# ProPrj_Iris_One_2026-02-20.net
KiCad netlist of a schematic drawn in EasyEDA Pro
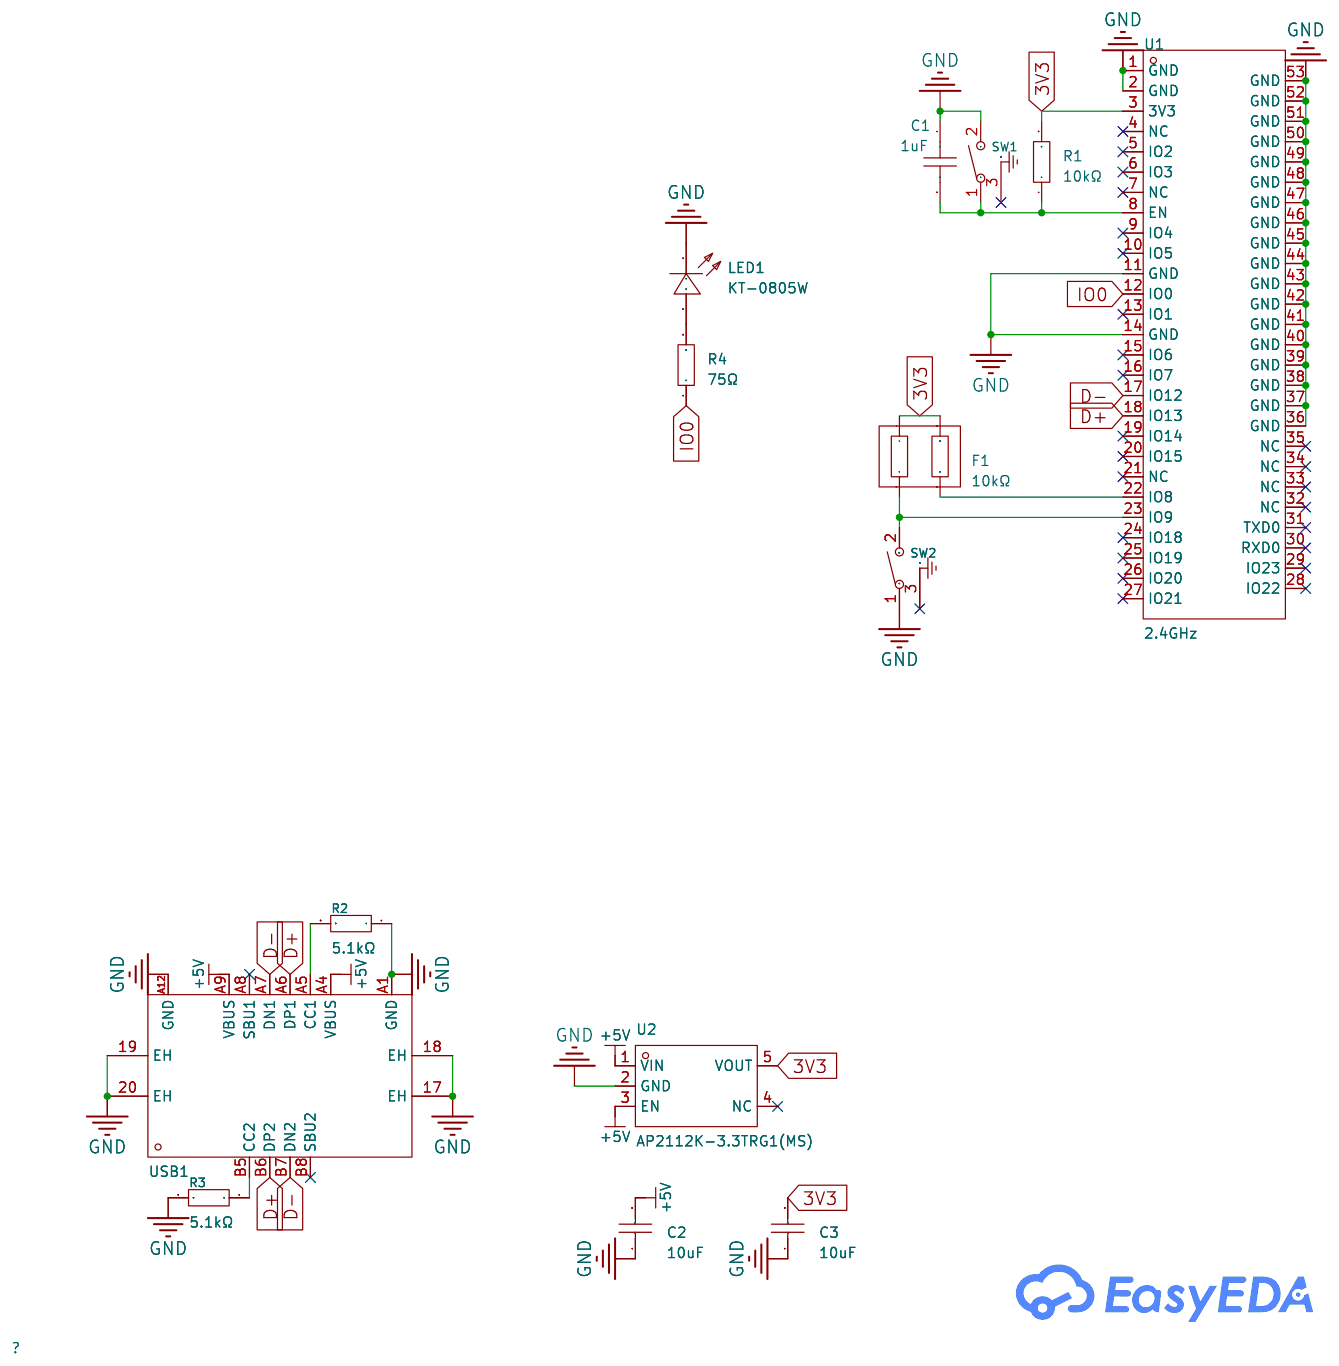
[diagram p0: schematic sheet]

(export (version "E")
  (design (tool "Eeschema 10.0.6"))
  (components
    (comp (ref "C1")
      (value "1uF")
      (footprint "easyedapro:C0402")
      (description "Capacitance:1uF Tolerance:±10% Tolerance:±10% Voltage Rating:25V Temperature Coefficient:X5R")
      (fields
        (field (name "Manufacturer Part") "CL05A105KA5NQNC")
        (field (name "Manufacturer") "SAMSUNG(三星)")
      )
      (libsource (lib "easyedapro") (part "CL05A105KA5NQNC"))
    )
    (comp (ref "C2")
      (value "10uF")
      (footprint "easyedapro:C0402")
      (description "Capacitance:10uF Tolerance:±20% Tolerance:±20% Voltage Rating:6.3V Temperature Coefficient:X5R")
      (fields
        (field (name "Manufacturer Part") "CL05A106MQ5NUNC")
        (field (name "Manufacturer") "SAMSUNG(三星)")
      )
      (libsource (lib "easyedapro") (part "CL05A106MQ5NUNC"))
    )
    (comp (ref "C3")
      (value "10uF")
      (footprint "easyedapro:C0402")
      (description "Capacitance:10uF Tolerance:±20% Tolerance:±20% Voltage Rating:6.3V Temperature Coefficient:X5R")
      (fields
        (field (name "Manufacturer Part") "CL05A106MQ5NUNC")
        (field (name "Manufacturer") "SAMSUNG(三星)")
      )
      (libsource (lib "easyedapro") (part "CL05A106MQ5NUNC"))
    )
    (comp (ref "F1")
      (value "10kΩ")
      (footprint "easyedapro:RES-ARRAY-SMD_0404-4P-L1.0-W1.0-BL")
      (fields (field (name "Manufacturer Part") "YC122-JR-0710KL") (field (name "Manufacturer") "YAGEO(国巨)"))
      (libsource (lib "easyedapro") (part "YC122-JR-0710KL"))
    )
    (comp (ref "LED1")
      (value "KT-0805W")
      (footprint "easyedapro:LED0805-R-RD")
      (fields (field (name "Manufacturer") "KENTO"))
      (libsource (lib "easyedapro") (part "whiteLEDSMD"))
    )
    (comp (ref "R1")
      (value "10kΩ")
      (footprint "easyedapro:R0402")
      (fields
        (field (name "Manufacturer Part") "0402WGF1002TCE")
        (field (name "Manufacturer") "UNI-ROYAL(厚声)")
      )
      (libsource (lib "easyedapro") (part "0402WGF1002TCE"))
    )
    (comp (ref "R2")
      (value "5.1kΩ")
      (footprint "easyedapro:R0402")
      (fields
        (field (name "Manufacturer Part") "0402WGF5101TCE")
        (field (name "Manufacturer") "UNI-ROYAL(厚声)")
      )
      (libsource (lib "easyedapro") (part "0402WGF5101TCE"))
    )
    (comp (ref "R3")
      (value "5.1kΩ")
      (footprint "easyedapro:R0402")
      (fields
        (field (name "Manufacturer Part") "0402WGF5101TCE")
        (field (name "Manufacturer") "UNI-ROYAL(厚声)")
      )
      (libsource (lib "easyedapro") (part "0402WGF5101TCE"))
    )
    (comp (ref "R4")
      (value "75Ω")
      (footprint "easyedapro:R0402")
      (fields
        (field (name "Manufacturer Part") "0402WGF750JTCE")
        (field (name "Manufacturer") "UNI-ROYAL(厚声)")
      )
      (libsource (lib "easyedapro") (part "0402WGF750JTCE"))
    )
    (comp (ref "SW1")
      (value "SKTDLHE010")
      (footprint "easyedapro:KEY-SMD_SKTDLHE010")
      (description "Circuit:SPST Actuator Style:Rectangle button Mounting Style:卧贴 With Lamp:- Mechanical Life:-")
      (fields (field (name "Manufacturer") "ALPSALPINE(阿尔卑斯阿尔派)"))
      (libsource (lib "easyedapro") (part "SKTDLHE010"))
    )
    (comp (ref "SW2")
      (value "SKTDLHE010")
      (footprint "easyedapro:KEY-SMD_SKTDLHE010")
      (description "Circuit:SPST Actuator Style:Rectangle button Mounting Style:卧贴 With Lamp:- Mechanical Life:-")
      (fields (field (name "Manufacturer") "ALPSALPINE(阿尔卑斯阿尔派)"))
      (libsource (lib "easyedapro") (part "SKTDLHE010"))
    )
    (comp (ref "U1")
      (value "2.4GHz")
      (footprint "easyedapro:WIFIM-SMD_61P-L16.6-W13.2-P0.80-ESP32-C6-MINI-1-N4")
      (fields
        (field (name "Manufacturer Part") "ESP32-C6-MINI-1-N4")
        (field (name "Manufacturer") "ESPRESSIF(乐鑫)")
      )
      (libsource (lib "easyedapro") (part "ESP32-C6-MINI-1-N4"))
    )
    (comp (ref "U2")
      (value "AP2112K-3.3TRG1(MS)")
      (footprint "easyedapro:SOT-23-5_L2.9-W1.6-P0.95-LS2.7-BR")
      (fields (field (name "Manufacturer") "MSKSEMI(美森科)"))
      (libsource (lib "easyedapro") (part "AP2112K-3.3TRG1(MS)"))
    )
    (comp (ref "USB1")
      (value "TYPE-C 16P QTGM027")
      (footprint "easyedapro:USB-C-SMD_TYPE-C-16P-QTGM027")
      (fields (field (name "Manufacturer") "SHOU HAN(首韩)"))
      (libsource (lib "easyedapro") (part "TYPE-C 16P QTGM027"))
    )
  )
  (nets
    (net (code "1") (name "+5V") (class "Default")
      (node (ref "C2") (pin "2") (pinfunction "2_2") (pintype "input"))
      (node (ref "U2") (pin "1") (pinfunction "VIN_1") (pintype "unspecified"))
      (node (ref "U2") (pin "3") (pinfunction "EN_3") (pintype "unspecified"))
      (node (ref "USB1") (pin "A4") (pinfunction "VBUS_A4") (pintype "unspecified"))
      (node (ref "USB1") (pin "A9") (pinfunction "VBUS_A9") (pintype "unspecified"))
    )
    (net (code "2") (name "3V3") (class "Default")
      (node (ref "C3") (pin "2") (pinfunction "2_2") (pintype "input"))
      (node (ref "F1") (pin "3") (pinfunction "3_3") (pintype "unspecified"))
      (node (ref "F1") (pin "4") (pinfunction "4_4") (pintype "unspecified"))
      (node (ref "R1") (pin "2") (pinfunction "2_2") (pintype "input"))
      (node (ref "U1") (pin "3") (pinfunction "3V3_3") (pintype "unspecified"))
      (node (ref "U2") (pin "5") (pinfunction "VOUT_5") (pintype "unspecified"))
    )
    (net (code "3") (name "D+") (class "Default")
      (node (ref "U1") (pin "18") (pinfunction "IO13_18") (pintype "unspecified"))
      (node (ref "USB1") (pin "A6") (pinfunction "DP1_A6") (pintype "unspecified"))
      (node (ref "USB1") (pin "B6") (pinfunction "DP2_B6") (pintype "unspecified"))
    )
    (net (code "4") (name "D-") (class "Default")
      (node (ref "U1") (pin "17") (pinfunction "IO12_17") (pintype "unspecified"))
      (node (ref "USB1") (pin "A7") (pinfunction "DN1_A7") (pintype "unspecified"))
      (node (ref "USB1") (pin "B7") (pinfunction "DN2_B7") (pintype "unspecified"))
    )
    (net (code "5") (name "GND") (class "Default")
      (node (ref "C1") (pin "1") (pinfunction "1_1") (pintype "unspecified"))
      (node (ref "C2") (pin "1") (pinfunction "1_1") (pintype "input"))
      (node (ref "C3") (pin "1") (pinfunction "1_1") (pintype "input"))
      (node (ref "LED1") (pin "2") (pinfunction "K_2") (pintype "unspecified"))
      (node (ref "R2") (pin "1") (pinfunction "1_1") (pintype "input"))
      (node (ref "R3") (pin "2") (pinfunction "2_2") (pintype "input"))
      (node (ref "SW1") (pin "2") (pinfunction "2_2") (pintype "input"))
      (node (ref "SW2") (pin "1") (pinfunction "1_1") (pintype "input"))
      (node (ref "U1") (pin "1") (pinfunction "GND_1") (pintype "unspecified"))
      (node (ref "U1") (pin "11") (pinfunction "GND_11") (pintype "unspecified"))
      (node (ref "U1") (pin "14") (pinfunction "GND_14") (pintype "unspecified"))
      (node (ref "U1") (pin "2") (pinfunction "GND_2") (pintype "unspecified"))
      (node (ref "U1") (pin "36") (pinfunction "GND_36") (pintype "unspecified"))
      (node (ref "U1") (pin "37") (pinfunction "GND_37") (pintype "unspecified"))
      (node (ref "U1") (pin "38") (pinfunction "GND_38") (pintype "unspecified"))
      (node (ref "U1") (pin "39") (pinfunction "GND_39") (pintype "unspecified"))
      (node (ref "U1") (pin "40") (pinfunction "GND_40") (pintype "unspecified"))
      (node (ref "U1") (pin "41") (pinfunction "GND_41") (pintype "unspecified"))
      (node (ref "U1") (pin "42") (pinfunction "GND_42") (pintype "unspecified"))
      (node (ref "U1") (pin "43") (pinfunction "GND_43") (pintype "unspecified"))
      (node (ref "U1") (pin "44") (pinfunction "GND_44") (pintype "unspecified"))
      (node (ref "U1") (pin "45") (pinfunction "GND_45") (pintype "unspecified"))
      (node (ref "U1") (pin "46") (pinfunction "GND_46") (pintype "unspecified"))
      (node (ref "U1") (pin "47") (pinfunction "GND_47") (pintype "unspecified"))
      (node (ref "U1") (pin "48") (pinfunction "GND_48") (pintype "unspecified"))
      (node (ref "U1") (pin "49") (pinfunction "GND_49") (pintype "unspecified"))
      (node (ref "U1") (pin "50") (pinfunction "GND_50") (pintype "unspecified"))
      (node (ref "U1") (pin "51") (pinfunction "GND_51") (pintype "unspecified"))
      (node (ref "U1") (pin "52") (pinfunction "GND_52") (pintype "unspecified"))
      (node (ref "U1") (pin "53") (pinfunction "GND_53") (pintype "unspecified"))
      (node (ref "U2") (pin "2") (pinfunction "GND_2") (pintype "unspecified"))
      (node (ref "USB1") (pin "17") (pinfunction "EH_17") (pintype "unspecified"))
      (node (ref "USB1") (pin "18") (pinfunction "EH_18") (pintype "unspecified"))
      (node (ref "USB1") (pin "19") (pinfunction "EH_19") (pintype "unspecified"))
      (node (ref "USB1") (pin "20") (pinfunction "EH_20") (pintype "unspecified"))
      (node (ref "USB1") (pin "A1") (pinfunction "GND_A1") (pintype "unspecified"))
      (node (ref "USB1") (pin "A12") (pinfunction "GND_A12") (pintype "unspecified"))
    )
    (net (code "6") (name "IO0") (class "Default")
      (node (ref "R4") (pin "1") (pinfunction "1_1") (pintype "input"))
      (node (ref "U1") (pin "12") (pinfunction "IO0_12") (pintype "unspecified"))
    )
    (net (code "7") (name "Net-(LED1-A)") (class "Default")
      (node (ref "LED1") (pin "1") (pinfunction "A_1") (pintype "unspecified"))
      (node (ref "R4") (pin "2") (pinfunction "2_2") (pintype "input"))
    )
    (net (code "8") (name "Net-(U1-EN)") (class "Default")
      (node (ref "C1") (pin "2") (pinfunction "2_2") (pintype "unspecified"))
      (node (ref "R1") (pin "1") (pinfunction "1_1") (pintype "input"))
      (node (ref "SW1") (pin "1") (pinfunction "1_1") (pintype "input"))
      (node (ref "U1") (pin "8") (pinfunction "EN_8") (pintype "unspecified"))
    )
    (net (code "9") (name "Net-(U1-IO8)") (class "Default")
      (node (ref "F1") (pin "2") (pinfunction "2_2") (pintype "unspecified"))
      (node (ref "U1") (pin "22") (pinfunction "IO8_22") (pintype "unspecified"))
    )
    (net (code "10") (name "Net-(U1-IO9)") (class "Default")
      (node (ref "F1") (pin "1") (pinfunction "1_1") (pintype "unspecified"))
      (node (ref "SW2") (pin "2") (pinfunction "2_2") (pintype "input"))
      (node (ref "U1") (pin "23") (pinfunction "IO9_23") (pintype "unspecified"))
    )
    (net (code "11") (name "Net-(USB1-CC1)") (class "Default")
      (node (ref "R2") (pin "2") (pinfunction "2_2") (pintype "input"))
      (node (ref "USB1") (pin "A5") (pinfunction "CC1_A5") (pintype "unspecified"))
    )
    (net (code "12") (name "Net-(USB1-CC2)") (class "Default")
      (node (ref "R3") (pin "1") (pinfunction "1_1") (pintype "input"))
      (node (ref "USB1") (pin "B5") (pinfunction "CC2_B5") (pintype "unspecified"))
    )
    (net (code "13") (name "unconnected-(SW1-GND-Pad3)") (class "Default")
      (node (ref "SW1") (pin "3") (pinfunction "GND_3") (pintype "input+no_connect"))
    )
    (net (code "14") (name "unconnected-(SW2-GND-Pad3)") (class "Default")
      (node (ref "SW2") (pin "3") (pinfunction "GND_3") (pintype "input+no_connect"))
    )
    (net (code "15") (name "unconnected-(U1-IO1-Pad13)") (class "Default")
      (node (ref "U1") (pin "13") (pinfunction "IO1_13") (pintype "unspecified+no_connect"))
    )
    (net (code "16") (name "unconnected-(U1-IO2-Pad5)") (class "Default")
      (node (ref "U1") (pin "5") (pinfunction "IO2_5") (pintype "unspecified+no_connect"))
    )
    (net (code "17") (name "unconnected-(U1-IO3-Pad6)") (class "Default")
      (node (ref "U1") (pin "6") (pinfunction "IO3_6") (pintype "unspecified+no_connect"))
    )
    (net (code "18") (name "unconnected-(U1-IO4-Pad9)") (class "Default")
      (node (ref "U1") (pin "9") (pinfunction "IO4_9") (pintype "unspecified+no_connect"))
    )
    (net (code "19") (name "unconnected-(U1-IO5-Pad10)") (class "Default")
      (node (ref "U1") (pin "10") (pinfunction "IO5_10") (pintype "unspecified+no_connect"))
    )
    (net (code "20") (name "unconnected-(U1-IO6-Pad15)") (class "Default")
      (node (ref "U1") (pin "15") (pinfunction "IO6_15") (pintype "unspecified+no_connect"))
    )
    (net (code "21") (name "unconnected-(U1-IO7-Pad16)") (class "Default")
      (node (ref "U1") (pin "16") (pinfunction "IO7_16") (pintype "unspecified+no_connect"))
    )
    (net (code "22") (name "unconnected-(U1-IO14-Pad19)") (class "Default")
      (node (ref "U1") (pin "19") (pinfunction "IO14_19") (pintype "unspecified+no_connect"))
    )
    (net (code "23") (name "unconnected-(U1-IO15-Pad20)") (class "Default")
      (node (ref "U1") (pin "20") (pinfunction "IO15_20") (pintype "unspecified+no_connect"))
    )
    (net (code "24") (name "unconnected-(U1-IO18-Pad24)") (class "Default")
      (node (ref "U1") (pin "24") (pinfunction "IO18_24") (pintype "unspecified+no_connect"))
    )
    (net (code "25") (name "unconnected-(U1-IO19-Pad25)") (class "Default")
      (node (ref "U1") (pin "25") (pinfunction "IO19_25") (pintype "unspecified+no_connect"))
    )
    (net (code "26") (name "unconnected-(U1-IO20-Pad26)") (class "Default")
      (node (ref "U1") (pin "26") (pinfunction "IO20_26") (pintype "unspecified+no_connect"))
    )
    (net (code "27") (name "unconnected-(U1-IO21-Pad27)") (class "Default")
      (node (ref "U1") (pin "27") (pinfunction "IO21_27") (pintype "unspecified+no_connect"))
    )
    (net (code "28") (name "unconnected-(U1-IO22-Pad28)") (class "Default")
      (node (ref "U1") (pin "28") (pinfunction "IO22_28") (pintype "unspecified+no_connect"))
    )
    (net (code "29") (name "unconnected-(U1-IO23-Pad29)") (class "Default")
      (node (ref "U1") (pin "29") (pinfunction "IO23_29") (pintype "unspecified+no_connect"))
    )
    (net (code "30") (name "unconnected-(U1-NC-Pad4)") (class "Default")
      (node (ref "U1") (pin "4") (pinfunction "NC_4") (pintype "unspecified+no_connect"))
    )
    (net (code "31") (name "unconnected-(U1-NC-Pad7)") (class "Default")
      (node (ref "U1") (pin "7") (pinfunction "NC_7") (pintype "unspecified+no_connect"))
    )
    (net (code "32") (name "unconnected-(U1-NC-Pad21)") (class "Default")
      (node (ref "U1") (pin "21") (pinfunction "NC_21") (pintype "unspecified+no_connect"))
    )
    (net (code "33") (name "unconnected-(U1-NC-Pad32)") (class "Default")
      (node (ref "U1") (pin "32") (pinfunction "NC_32") (pintype "unspecified+no_connect"))
    )
    (net (code "34") (name "unconnected-(U1-NC-Pad33)") (class "Default")
      (node (ref "U1") (pin "33") (pinfunction "NC_33") (pintype "unspecified+no_connect"))
    )
    (net (code "35") (name "unconnected-(U1-NC-Pad34)") (class "Default")
      (node (ref "U1") (pin "34") (pinfunction "NC_34") (pintype "unspecified+no_connect"))
    )
    (net (code "36") (name "unconnected-(U1-NC-Pad35)") (class "Default")
      (node (ref "U1") (pin "35") (pinfunction "NC_35") (pintype "unspecified+no_connect"))
    )
    (net (code "37") (name "unconnected-(U1-RXD0-Pad30)") (class "Default")
      (node (ref "U1") (pin "30") (pinfunction "RXD0_30") (pintype "unspecified+no_connect"))
    )
    (net (code "38") (name "unconnected-(U1-TXD0-Pad31)") (class "Default")
      (node (ref "U1") (pin "31") (pinfunction "TXD0_31") (pintype "unspecified+no_connect"))
    )
    (net (code "39") (name "unconnected-(U2-NC-Pad4)") (class "Default")
      (node (ref "U2") (pin "4") (pinfunction "NC_4") (pintype "unspecified+no_connect"))
    )
    (net (code "40") (name "unconnected-(USB1-SBU1-PadA8)") (class "Default")
      (node (ref "USB1") (pin "A8") (pinfunction "SBU1_A8") (pintype "unspecified+no_connect"))
    )
    (net (code "41") (name "unconnected-(USB1-SBU2-PadB8)") (class "Default")
      (node (ref "USB1") (pin "B8") (pinfunction "SBU2_B8") (pintype "unspecified+no_connect"))
    )
  )
)
